# microcontroller.net
KiCad netlist of a schematic drawn in EAGLE
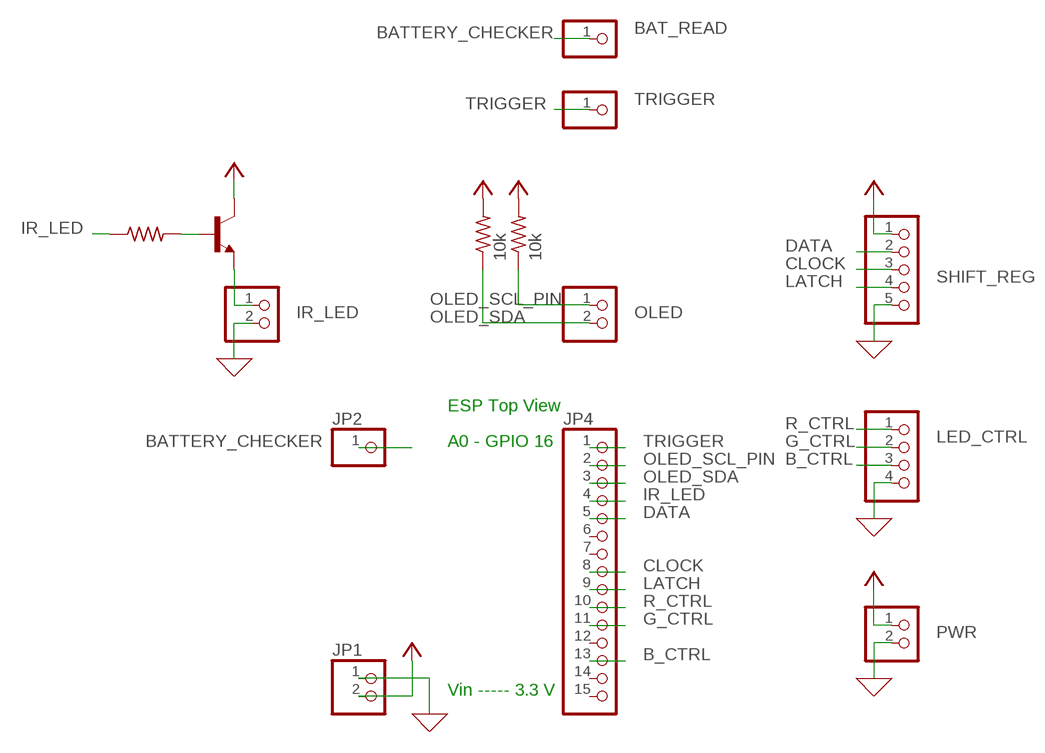
[diagram p0: schematic, sheet 1]

(export (version "E")
  (design (tool "Eeschema 10.0.6"))
  (components
    (comp (ref "BAT_READ")
      (value "PINHD-1X1")
      (footprint "eagle-import:1X01")
      (libsource (lib "eagle-import") (part "PINHD-1X1"))
    )
    (comp (ref "IR_LED")
      (value "PINHD-1X2")
      (footprint "eagle-import:1X02")
      (libsource (lib "eagle-import") (part "PINHD-1X2"))
    )
    (comp (ref "IR_TRS")
      (value "2N5088")
      (footprint "eagle-import:TO92")
      (libsource (lib "eagle-import") (part "2N5088"))
    )
    (comp (ref "JP1")
      (value "PINHD-1X2")
      (footprint "eagle-import:1X02")
      (libsource (lib "eagle-import") (part "PINHD-1X2"))
    )
    (comp (ref "JP2")
      (value "PINHD-1X1")
      (footprint "eagle-import:1X01")
      (libsource (lib "eagle-import") (part "PINHD-1X1"))
    )
    (comp (ref "JP4")
      (value "PINHD-1X15")
      (footprint "eagle-import:1X15")
      (libsource (lib "eagle-import") (part "PINHD-1X15"))
    )
    (comp (ref "LED_CTRL")
      (value "PINHD-1X4")
      (footprint "eagle-import:1X04")
      (libsource (lib "eagle-import") (part "PINHD-1X4"))
    )
    (comp (ref "OLED")
      (value "PINHD-1X2")
      (footprint "eagle-import:1X02")
      (libsource (lib "eagle-import") (part "PINHD-1X2"))
    )
    (comp (ref "PWR")
      (value "PINHD-1X2")
      (footprint "eagle-import:1X02")
      (libsource (lib "eagle-import") (part "PINHD-1X2"))
    )
    (comp (ref "R1")
      (value "10k")
      (footprint "eagle-import:0204_7")
      (libsource (lib "eagle-import") (part "R-US_0204/7"))
    )
    (comp (ref "R2")
      (value "10k")
      (footprint "eagle-import:0204_7")
      (libsource (lib "eagle-import") (part "R-US_0204/7"))
    )
    (comp (ref "R3")
      (value "R-US_0204/7")
      (footprint "eagle-import:0204_7")
      (libsource (lib "eagle-import") (part "R-US_0204/7"))
    )
    (comp (ref "SHIFT_REG")
      (value "PINHD-1X5")
      (footprint "eagle-import:1X05")
      (libsource (lib "eagle-import") (part "PINHD-1X5"))
    )
    (comp (ref "TRIGGER")
      (value "PINHD-1X1")
      (footprint "eagle-import:1X01")
      (libsource (lib "eagle-import") (part "PINHD-1X1"))
    )
  )
  (nets
    (net (code "1") (name "/BATTERY_CHECKER") (class "Default")
      (node (ref "BAT_READ") (pin "1") (pinfunction "1_1") (pintype "passive"))
      (node (ref "JP2") (pin "1") (pinfunction "1_1") (pintype "passive"))
    )
    (net (code "2") (name "/B_CTRL") (class "Default")
      (node (ref "JP4") (pin "13") (pinfunction "13_13") (pintype "passive"))
      (node (ref "LED_CTRL") (pin "3") (pinfunction "3_3") (pintype "passive"))
    )
    (net (code "3") (name "/CLOCK") (class "Default")
      (node (ref "JP4") (pin "8") (pinfunction "8_8") (pintype "passive"))
      (node (ref "SHIFT_REG") (pin "3") (pinfunction "3_3") (pintype "passive"))
    )
    (net (code "4") (name "/DATA") (class "Default")
      (node (ref "JP4") (pin "5") (pinfunction "5_5") (pintype "passive"))
      (node (ref "SHIFT_REG") (pin "2") (pinfunction "2_2") (pintype "passive"))
    )
    (net (code "5") (name "/G_CTRL") (class "Default")
      (node (ref "JP4") (pin "11") (pinfunction "11_11") (pintype "passive"))
      (node (ref "LED_CTRL") (pin "2") (pinfunction "2_2") (pintype "passive"))
    )
    (net (code "6") (name "/IR_LED") (class "Default")
      (node (ref "JP4") (pin "4") (pinfunction "4_4") (pintype "passive"))
      (node (ref "R3") (pin "1") (pinfunction "1_1") (pintype "passive"))
    )
    (net (code "7") (name "/LATCH") (class "Default")
      (node (ref "JP4") (pin "9") (pinfunction "9_9") (pintype "passive"))
      (node (ref "SHIFT_REG") (pin "4") (pinfunction "4_4") (pintype "passive"))
    )
    (net (code "8") (name "/OLED_SCL_PIN") (class "Default")
      (node (ref "JP4") (pin "2") (pinfunction "2_2") (pintype "passive"))
      (node (ref "OLED") (pin "1") (pinfunction "1_1") (pintype "passive"))
      (node (ref "R1") (pin "1") (pinfunction "1_1") (pintype "passive"))
    )
    (net (code "9") (name "/OLED_SDA") (class "Default")
      (node (ref "JP4") (pin "3") (pinfunction "3_3") (pintype "passive"))
      (node (ref "OLED") (pin "2") (pinfunction "2_2") (pintype "passive"))
      (node (ref "R2") (pin "1") (pinfunction "1_1") (pintype "passive"))
    )
    (net (code "10") (name "/R_CTRL") (class "Default")
      (node (ref "JP4") (pin "10") (pinfunction "10_10") (pintype "passive"))
      (node (ref "LED_CTRL") (pin "1") (pinfunction "1_1") (pintype "passive"))
    )
    (net (code "11") (name "/TRIGGER") (class "Default")
      (node (ref "JP4") (pin "1") (pinfunction "1_1") (pintype "passive"))
      (node (ref "TRIGGER") (pin "1") (pinfunction "1_1") (pintype "passive"))
    )
    (net (code "12") (name "GND") (class "Default")
      (node (ref "IR_LED") (pin "2") (pinfunction "2_2") (pintype "passive"))
      (node (ref "JP1") (pin "1") (pinfunction "1_1") (pintype "passive"))
      (node (ref "LED_CTRL") (pin "4") (pinfunction "4_4") (pintype "passive"))
      (node (ref "PWR") (pin "2") (pinfunction "2_2") (pintype "passive"))
      (node (ref "SHIFT_REG") (pin "5") (pinfunction "5_5") (pintype "passive"))
    )
    (net (code "13") (name "Net-(IR_TRS-B)") (class "Default")
      (node (ref "IR_TRS") (pin "2") (pinfunction "B_2") (pintype "passive"))
      (node (ref "R3") (pin "2") (pinfunction "2_2") (pintype "passive"))
    )
    (net (code "14") (name "Net-(IR_TRS-E)") (class "Default")
      (node (ref "IR_LED") (pin "1") (pinfunction "1_1") (pintype "passive"))
      (node (ref "IR_TRS") (pin "3") (pinfunction "E_3") (pintype "passive"))
    )
    (net (code "15") (name "VCC") (class "Default")
      (node (ref "IR_TRS") (pin "1") (pinfunction "C_1") (pintype "passive"))
      (node (ref "JP1") (pin "2") (pinfunction "2_2") (pintype "passive"))
      (node (ref "PWR") (pin "1") (pinfunction "1_1") (pintype "passive"))
      (node (ref "R1") (pin "2") (pinfunction "2_2") (pintype "passive"))
      (node (ref "R2") (pin "2") (pinfunction "2_2") (pintype "passive"))
      (node (ref "SHIFT_REG") (pin "1") (pinfunction "1_1") (pintype "passive"))
    )
    (net (code "16") (name "unconnected-(JP4-Pad6)") (class "Default")
      (node (ref "JP4") (pin "6") (pinfunction "6_6") (pintype "passive"))
    )
    (net (code "17") (name "unconnected-(JP4-Pad7)") (class "Default")
      (node (ref "JP4") (pin "7") (pinfunction "7_7") (pintype "passive"))
    )
    (net (code "18") (name "unconnected-(JP4-Pad12)") (class "Default")
      (node (ref "JP4") (pin "12") (pinfunction "12_12") (pintype "passive"))
    )
    (net (code "19") (name "unconnected-(JP4-Pad14)") (class "Default")
      (node (ref "JP4") (pin "14") (pinfunction "14_14") (pintype "passive"))
    )
    (net (code "20") (name "unconnected-(JP4-Pad15)") (class "Default")
      (node (ref "JP4") (pin "15") (pinfunction "15_15") (pintype "passive"))
    )
  )
)
